# ACCELEROMETER.net
KiCad netlist of a schematic drawn in Altium Designer
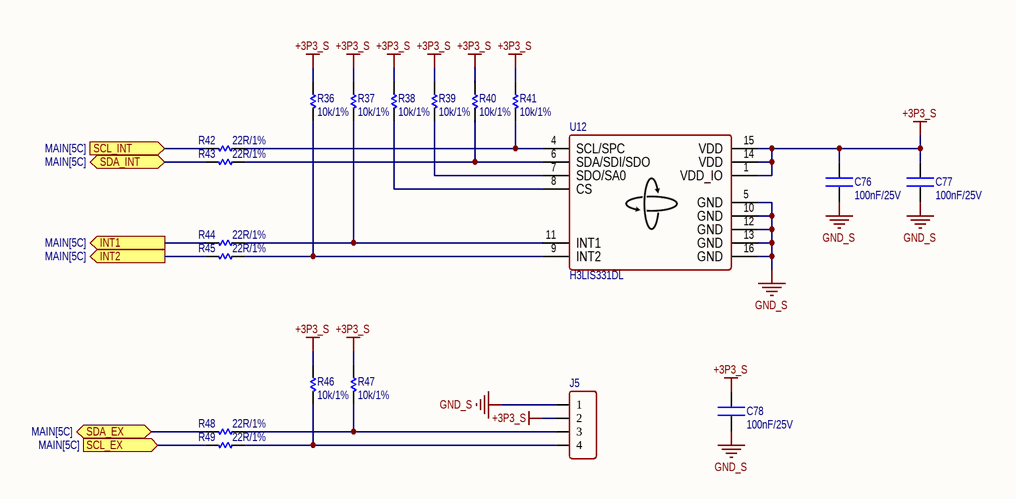
[diagram p0: ACCELEROMETER.SchDoc]

(export (version "E")
  (design (tool "Eeschema 10.0.6"))
  (components
    (comp (ref "C76")
      (value "100nF/25V")
      (footprint "CN-SMD-0603")
      (description "CL10B104KA8NNNC")
      (libsource (lib "Library") (part "CN"))
    )
    (comp (ref "C77")
      (value "100nF/25V")
      (footprint "CN-SMD-0603")
      (description "CL10B104KA8NNNC")
      (libsource (lib "Library") (part "CN"))
    )
    (comp (ref "C78")
      (value "100nF/25V")
      (footprint "CN-SMD-0603")
      (description "CL10B104KA8NNNC")
      (libsource (lib "Library") (part "CN"))
    )
    (comp (ref "J5")
      (value "SM04B-SRSS-TBLFSN")
      (footprint "BM04B-SRSS-TB")
      (libsource (lib "Library") (part "Header4"))
    )
    (comp (ref "R36")
      (value "10k/1%")
      (footprint "RES-SMD-0603")
      (description "ERJ-3EKF1002V")
      (fields
        (field (name "MANUFACTURER") "Generic Components")
        (field (name "PUBLISHER") "Altium Hobart Technology Centre")
      )
      (libsource (lib "Library") (part "Res-SMD"))
    )
    (comp (ref "R37")
      (value "10k/1%")
      (footprint "RES-SMD-0603")
      (description "ERJ-3EKF1002V")
      (fields
        (field (name "MANUFACTURER") "Generic Components")
        (field (name "PUBLISHER") "Altium Hobart Technology Centre")
      )
      (libsource (lib "Library") (part "Res-SMD"))
    )
    (comp (ref "R38")
      (value "10k/1%")
      (footprint "RES-SMD-0603")
      (description "ERJ-3EKF1002V")
      (fields
        (field (name "MANUFACTURER") "Generic Components")
        (field (name "PUBLISHER") "Altium Hobart Technology Centre")
      )
      (libsource (lib "Library") (part "Res-SMD"))
    )
    (comp (ref "R39")
      (value "10k/1%")
      (footprint "RES-SMD-0603")
      (description "ERJ-3EKF1002V")
      (fields
        (field (name "MANUFACTURER") "Generic Components")
        (field (name "PUBLISHER") "Altium Hobart Technology Centre")
      )
      (libsource (lib "Library") (part "Res-SMD"))
    )
    (comp (ref "R40")
      (value "10k/1%")
      (footprint "RES-SMD-0603")
      (description "ERJ-3EKF1002V")
      (fields
        (field (name "MANUFACTURER") "Generic Components")
        (field (name "PUBLISHER") "Altium Hobart Technology Centre")
      )
      (libsource (lib "Library") (part "Res-SMD"))
    )
    (comp (ref "R41")
      (value "10k/1%")
      (footprint "RES-SMD-0603")
      (description "ERJ-3EKF1002V")
      (fields
        (field (name "MANUFACTURER") "Generic Components")
        (field (name "PUBLISHER") "Altium Hobart Technology Centre")
      )
      (libsource (lib "Library") (part "Res-SMD"))
    )
    (comp (ref "R42")
      (value "22R/1%")
      (footprint "RES-SMD-0603")
      (description "ERJ-3EKF22R0V")
      (libsource (lib "Library") (part "Res-SMD"))
    )
    (comp (ref "R43")
      (value "22R/1%")
      (footprint "RES-SMD-0603")
      (description "ERJ-3EKF22R0V")
      (libsource (lib "Library") (part "Res-SMD"))
    )
    (comp (ref "R44")
      (value "22R/1%")
      (footprint "RES-SMD-0603")
      (description "ERJ-3EKF22R0V")
      (libsource (lib "Library") (part "Res-SMD"))
    )
    (comp (ref "R45")
      (value "22R/1%")
      (footprint "RES-SMD-0603")
      (description "ERJ-3EKF22R0V")
      (libsource (lib "Library") (part "Res-SMD"))
    )
    (comp (ref "R46")
      (value "10k/1%")
      (footprint "RES-SMD-0603")
      (description "ERJ-3EKF1002V")
      (fields
        (field (name "MANUFACTURER") "Generic Components")
        (field (name "PUBLISHER") "Altium Hobart Technology Centre")
      )
      (libsource (lib "Library") (part "Res-SMD"))
    )
    (comp (ref "R47")
      (value "10k/1%")
      (footprint "RES-SMD-0603")
      (description "ERJ-3EKF1002V")
      (fields
        (field (name "MANUFACTURER") "Generic Components")
        (field (name "PUBLISHER") "Altium Hobart Technology Centre")
      )
      (libsource (lib "Library") (part "Res-SMD"))
    )
    (comp (ref "R48")
      (value "22R/1%")
      (footprint "RES-SMD-0603")
      (description "ERJ-3EKF22R0V")
      (libsource (lib "Library") (part "Res-SMD"))
    )
    (comp (ref "R49")
      (value "22R/1%")
      (footprint "RES-SMD-0603")
      (description "ERJ-3EKF22R0V")
      (libsource (lib "Library") (part "Res-SMD"))
    )
    (comp (ref "U12")
      (value "H3LIS331DL")
      (footprint "TFLGA-16L")
      (description "High-g, low-power 3-axis digital accelerometer")
      (libsource (lib "Library") (part "H3LIS331DL"))
    )
  )
  (nets
    (net (code "1") (name "+3P3_S") (class "Default")
      (node (ref "C76") (pin "2") (pinfunction "2_2") (pintype "passive"))
      (node (ref "C77") (pin "2") (pinfunction "2_2") (pintype "passive"))
      (node (ref "C78") (pin "2") (pinfunction "2_2") (pintype "passive"))
      (node (ref "J5") (pin "2") (pinfunction "2_2") (pintype "passive"))
      (node (ref "R36") (pin "1") (pinfunction "1_1") (pintype "passive"))
      (node (ref "R37") (pin "1") (pinfunction "1_1") (pintype "passive"))
      (node (ref "R38") (pin "1") (pinfunction "1_1") (pintype "passive"))
      (node (ref "R39") (pin "1") (pinfunction "1_1") (pintype "passive"))
      (node (ref "R40") (pin "1") (pinfunction "1_1") (pintype "passive"))
      (node (ref "R41") (pin "1") (pinfunction "1_1") (pintype "passive"))
      (node (ref "R46") (pin "1") (pinfunction "1_1") (pintype "passive"))
      (node (ref "R47") (pin "1") (pinfunction "1_1") (pintype "passive"))
      (node (ref "U12") (pin "1") (pinfunction "VDD_IO_1") (pintype "passive"))
      (node (ref "U12") (pin "14") (pinfunction "VDD_14") (pintype "passive"))
      (node (ref "U12") (pin "15") (pinfunction "VDD_15") (pintype "passive"))
    )
    (net (code "2") (name "/INT1") (class "Default")
      (node (ref "R44") (pin "2") (pinfunction "2_2") (pintype "passive"))
    )
    (net (code "3") (name "/INT2") (class "Default")
      (node (ref "R45") (pin "2") (pinfunction "2_2") (pintype "passive"))
    )
    (net (code "4") (name "/SCL_EX") (class "Default")
      (node (ref "R49") (pin "2") (pinfunction "2_2") (pintype "passive"))
    )
    (net (code "5") (name "/SCL_INT") (class "Default")
      (node (ref "R42") (pin "2") (pinfunction "2_2") (pintype "passive"))
    )
    (net (code "6") (name "/SDA_EX") (class "Default")
      (node (ref "R48") (pin "2") (pinfunction "2_2") (pintype "passive"))
    )
    (net (code "7") (name "/SDA_INT") (class "Default")
      (node (ref "R43") (pin "2") (pinfunction "2_2") (pintype "passive"))
    )
    (net (code "8") (name "GND_S") (class "Default")
      (node (ref "C76") (pin "1") (pinfunction "1_1") (pintype "passive"))
      (node (ref "C77") (pin "1") (pinfunction "1_1") (pintype "passive"))
      (node (ref "C78") (pin "1") (pinfunction "1_1") (pintype "passive"))
      (node (ref "J5") (pin "1") (pinfunction "1_1") (pintype "passive"))
      (node (ref "U12") (pin "10") (pinfunction "GND_10") (pintype "passive"))
      (node (ref "U12") (pin "12") (pinfunction "GND_12") (pintype "passive"))
      (node (ref "U12") (pin "13") (pinfunction "GND_13") (pintype "passive"))
      (node (ref "U12") (pin "16") (pinfunction "GND_16") (pintype "passive"))
      (node (ref "U12") (pin "5") (pinfunction "GND_5") (pintype "passive"))
    )
    (net (code "9") (name "Net-(J5-Pad3)") (class "Default")
      (node (ref "J5") (pin "3") (pinfunction "3_3") (pintype "passive"))
      (node (ref "R47") (pin "2") (pinfunction "2_2") (pintype "passive"))
      (node (ref "R48") (pin "1") (pinfunction "1_1") (pintype "passive"))
    )
    (net (code "10") (name "Net-(J5-Pad4)") (class "Default")
      (node (ref "J5") (pin "4") (pinfunction "4_4") (pintype "passive"))
      (node (ref "R46") (pin "2") (pinfunction "2_2") (pintype "passive"))
      (node (ref "R49") (pin "1") (pinfunction "1_1") (pintype "passive"))
    )
    (net (code "11") (name "Net-(U12-CS)") (class "Default")
      (node (ref "R38") (pin "2") (pinfunction "2_2") (pintype "passive"))
      (node (ref "U12") (pin "8") (pinfunction "CS_8") (pintype "passive"))
    )
    (net (code "12") (name "Net-(U12-INT1)") (class "Default")
      (node (ref "R37") (pin "2") (pinfunction "2_2") (pintype "passive"))
      (node (ref "R44") (pin "1") (pinfunction "1_1") (pintype "passive"))
      (node (ref "U12") (pin "11") (pinfunction "INT1_11") (pintype "passive"))
    )
    (net (code "13") (name "Net-(U12-INT2)") (class "Default")
      (node (ref "R36") (pin "2") (pinfunction "2_2") (pintype "passive"))
      (node (ref "R45") (pin "1") (pinfunction "1_1") (pintype "passive"))
      (node (ref "U12") (pin "9") (pinfunction "INT2_9") (pintype "passive"))
    )
    (net (code "14") (name "Net-(U12-SCL{slash}SPC)") (class "Default")
      (node (ref "R41") (pin "2") (pinfunction "2_2") (pintype "passive"))
      (node (ref "R42") (pin "1") (pinfunction "1_1") (pintype "passive"))
      (node (ref "U12") (pin "4") (pinfunction "SCL/SPC_4") (pintype "passive"))
    )
    (net (code "15") (name "Net-(U12-SDA{slash}SDI{slash}SDO)") (class "Default")
      (node (ref "R40") (pin "2") (pinfunction "2_2") (pintype "passive"))
      (node (ref "R43") (pin "1") (pinfunction "1_1") (pintype "passive"))
      (node (ref "U12") (pin "6") (pinfunction "SDA/SDI/SDO_6") (pintype "passive"))
    )
    (net (code "16") (name "Net-(U12-SDO{slash}SA0)") (class "Default")
      (node (ref "R39") (pin "2") (pinfunction "2_2") (pintype "passive"))
      (node (ref "U12") (pin "7") (pinfunction "SDO/SA0_7") (pintype "passive"))
    )
  )
)
